# I2C.net
KiCad netlist of a schematic drawn in Altium Designer
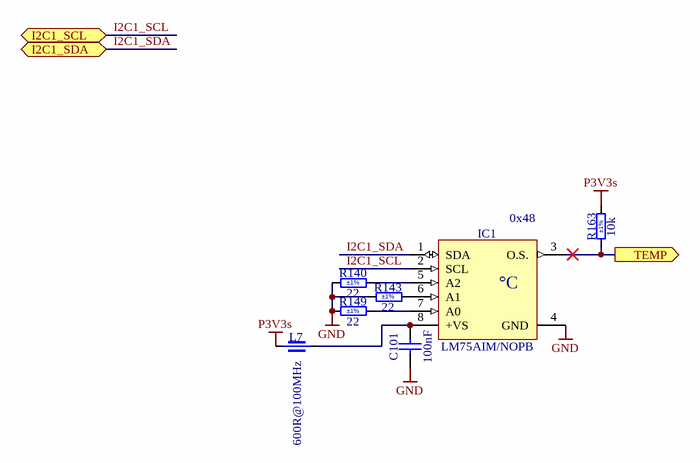
[diagram p0: I2C.SchDoc]

(export (version "E")
  (design (tool "Eeschema 10.0.6"))
  (components
    (comp (ref "C101")
      (value "100nF")
      (footprint "CAPC1608X87N")
      (description "Non-polarised capacitor")
      (fields
        (field (name "PART NUMBER") "CC0603_100NF_50V_10%_X7R")
        (field (name "VOLTAGE") "50V")
        (field (name "AUTHOR") "CERN DEM JLC")
      )
      (libsource (lib "Capacitors") (part "Capacitor - non polarized"))
    )
    (comp (ref "IC1")
      (value "LM75AIM/NOPB")
      (footprint "SOIC127P600X175-8N")
      (description "Digital Temperature Sensor and Thermal Watchdog with Two-Wire Interface")
      (fields (field (name "MANUFACTURER") "TEXAS INSTRUMENTS") (field (name "AUTHOR") "CERN DEM JLC"))
      (libsource (lib "ICs And Semiconductors") (part "LM75"))
    )
    (comp (ref "L7")
      (value "600R@100MHz")
      (footprint "INDC1608X95N")
      (fields
        (field (name "PART NUMBER") "IND0603_MURATA_BLM18AG601SN1")
        (field (name "POWER") "500mA")
        (field (name "TOLERANCE") "±25%")
        (field (name "AUTHOR") "CERN DEM MR")
      )
      (libsource (lib "Inductors & Transformers") (part "Ferrite Bead"))
    )
    (comp (ref "R140")
      (value "22")
      (footprint "RESC1608X55N")
      (description "Resistor - 1%")
      (fields
        (field (name "TOLERANCE") "±1%")
        (field (name "PART NUMBER") "R0603_22R_1%_0.1W_100PPM")
        (field (name "POWER") "0.1W")
        (field (name "AUTHOR") "CERN DEM JLC")
      )
      (libsource (lib "Resistors") (part "Resistor - 1%"))
    )
    (comp (ref "R143")
      (value "22")
      (footprint "RESC1608X55N")
      (description "Resistor - 1%")
      (fields
        (field (name "TOLERANCE") "±1%")
        (field (name "PART NUMBER") "R0603_22R_1%_0.1W_100PPM")
        (field (name "POWER") "0.1W")
        (field (name "AUTHOR") "CERN DEM JLC")
      )
      (libsource (lib "Resistors") (part "Resistor - 1%"))
    )
    (comp (ref "R149")
      (value "22")
      (footprint "RESC1608X55N")
      (description "Resistor - 1%")
      (fields
        (field (name "TOLERANCE") "±1%")
        (field (name "PART NUMBER") "R0603_22R_1%_0.1W_100PPM")
        (field (name "POWER") "0.1W")
        (field (name "AUTHOR") "CERN DEM JLC")
      )
      (libsource (lib "Resistors") (part "Resistor - 1%"))
    )
    (comp (ref "R163")
      (value "10k")
      (footprint "RESC1005X40N")
      (description "Resistor - 1%")
      (fields
        (field (name "TOLERANCE") "±1%")
        (field (name "PART NUMBER") "R0402_10K_1%_0.0625W_100PPM")
        (field (name "POWER") "0.0625W")
        (field (name "AUTHOR") "CERN DEM JLC")
      )
      (libsource (lib "Resistors") (part "Resistor - 1%"))
    )
  )
  (nets
    (net (code "1") (name "/I2C1_SCL") (class "Default")
      (node (ref "IC1") (pin "2") (pinfunction "SCL_2") (pintype "input"))
    )
    (net (code "2") (name "/I2C1_SDA") (class "Default")
      (node (ref "IC1") (pin "1") (pinfunction "SDA_1") (pintype "bidirectional"))
    )
    (net (code "3") (name "/TEMP") (class "Default")
      (node (ref "IC1") (pin "3") (pinfunction "O.S._3") (pintype "output"))
      (node (ref "R163") (pin "1") (pinfunction "1_1") (pintype "passive"))
    )
    (net (code "4") (name "GND") (class "Default")
      (node (ref "C101") (pin "1") (pinfunction "1_1") (pintype "passive"))
      (node (ref "IC1") (pin "4") (pinfunction "GND_4") (pintype "power_in"))
      (node (ref "R140") (pin "1") (pinfunction "1_1") (pintype "passive"))
      (node (ref "R143") (pin "1") (pinfunction "1_1") (pintype "passive"))
      (node (ref "R149") (pin "1") (pinfunction "1_1") (pintype "passive"))
    )
    (net (code "5") (name "Net-(IC1-+VS)") (class "Default")
      (node (ref "C101") (pin "2") (pinfunction "2_2") (pintype "passive"))
      (node (ref "IC1") (pin "8") (pinfunction "+VS_8") (pintype "power_in"))
      (node (ref "L7") (pin "2") (pinfunction "2_2") (pintype "passive"))
    )
    (net (code "6") (name "Net-(IC1-A0)") (class "Default")
      (node (ref "IC1") (pin "7") (pinfunction "A0_7") (pintype "input"))
      (node (ref "R149") (pin "2") (pinfunction "2_2") (pintype "passive"))
    )
    (net (code "7") (name "Net-(IC1-A1)") (class "Default")
      (node (ref "IC1") (pin "6") (pinfunction "A1_6") (pintype "input"))
      (node (ref "R143") (pin "2") (pinfunction "2_2") (pintype "passive"))
    )
    (net (code "8") (name "Net-(IC1-A2)") (class "Default")
      (node (ref "IC1") (pin "5") (pinfunction "A2_5") (pintype "input"))
      (node (ref "R140") (pin "2") (pinfunction "2_2") (pintype "passive"))
    )
    (net (code "9") (name "P3V3s") (class "Default")
      (node (ref "L7") (pin "1") (pinfunction "1_1") (pintype "passive"))
      (node (ref "R163") (pin "2") (pinfunction "2_2") (pintype "passive"))
    )
  )
)
